# ICD_ADAPTER.net
KiCad netlist of a schematic drawn in Altium Designer
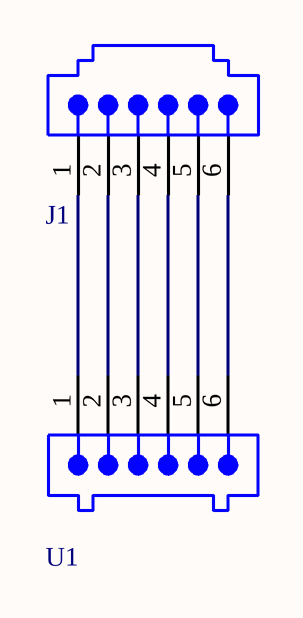
[diagram p0: ICD_ADAPTER.SchDoc]

(export (version "E")
  (design (tool "Eeschema 10.0.6"))
  (components
    (comp (ref "J1")
      (value "CONN MOD JACK 6-6 RT/A PCB 50AU")
      (footprint "43202-6101")
      (fields
        (field (name "MANUFACTURER") "Tyco Electronics Amp")
        (field (name "MANUFACTURER PART NUMBER") "5555165-1")
        (field (name "SOURCE") "Digikey")
      )
      (libsource (lib "Playworld") (part "Microchip ICD2"))
    )
    (comp (ref "U1")
      (value "1786446")
      (footprint "1786446")
      (fields (field (name "SOURCE") "Digikey"))
      (libsource (lib "Playworld") (part "1786446"))
    )
  )
  (nets
    (net (code "1") (name "Net-(J1-Pad1)") (class "Default")
      (node (ref "J1") (pin "1") (pinfunction "1_1") (pintype "passive"))
      (node (ref "U1") (pin "1") (pinfunction "1_1") (pintype "passive"))
    )
    (net (code "2") (name "Net-(J1-Pad2)") (class "Default")
      (node (ref "J1") (pin "2") (pinfunction "2_2") (pintype "passive"))
      (node (ref "U1") (pin "2") (pinfunction "2_2") (pintype "passive"))
    )
    (net (code "3") (name "Net-(J1-Pad3)") (class "Default")
      (node (ref "J1") (pin "3") (pinfunction "3_3") (pintype "passive"))
      (node (ref "U1") (pin "3") (pinfunction "3_3") (pintype "passive"))
    )
    (net (code "4") (name "Net-(J1-Pad4)") (class "Default")
      (node (ref "J1") (pin "4") (pinfunction "4_4") (pintype "passive"))
      (node (ref "U1") (pin "4") (pinfunction "4_4") (pintype "passive"))
    )
    (net (code "5") (name "Net-(J1-Pad5)") (class "Default")
      (node (ref "J1") (pin "5") (pinfunction "5_5") (pintype "passive"))
      (node (ref "U1") (pin "5") (pinfunction "5_5") (pintype "passive"))
    )
    (net (code "6") (name "Net-(J1-Pad6)") (class "Default")
      (node (ref "J1") (pin "6") (pinfunction "6_6") (pintype "passive"))
      (node (ref "U1") (pin "6") (pinfunction "6_6") (pintype "passive"))
    )
  )
)
